# sch2.net
KiCad netlist of a schematic drawn in Altium Designer
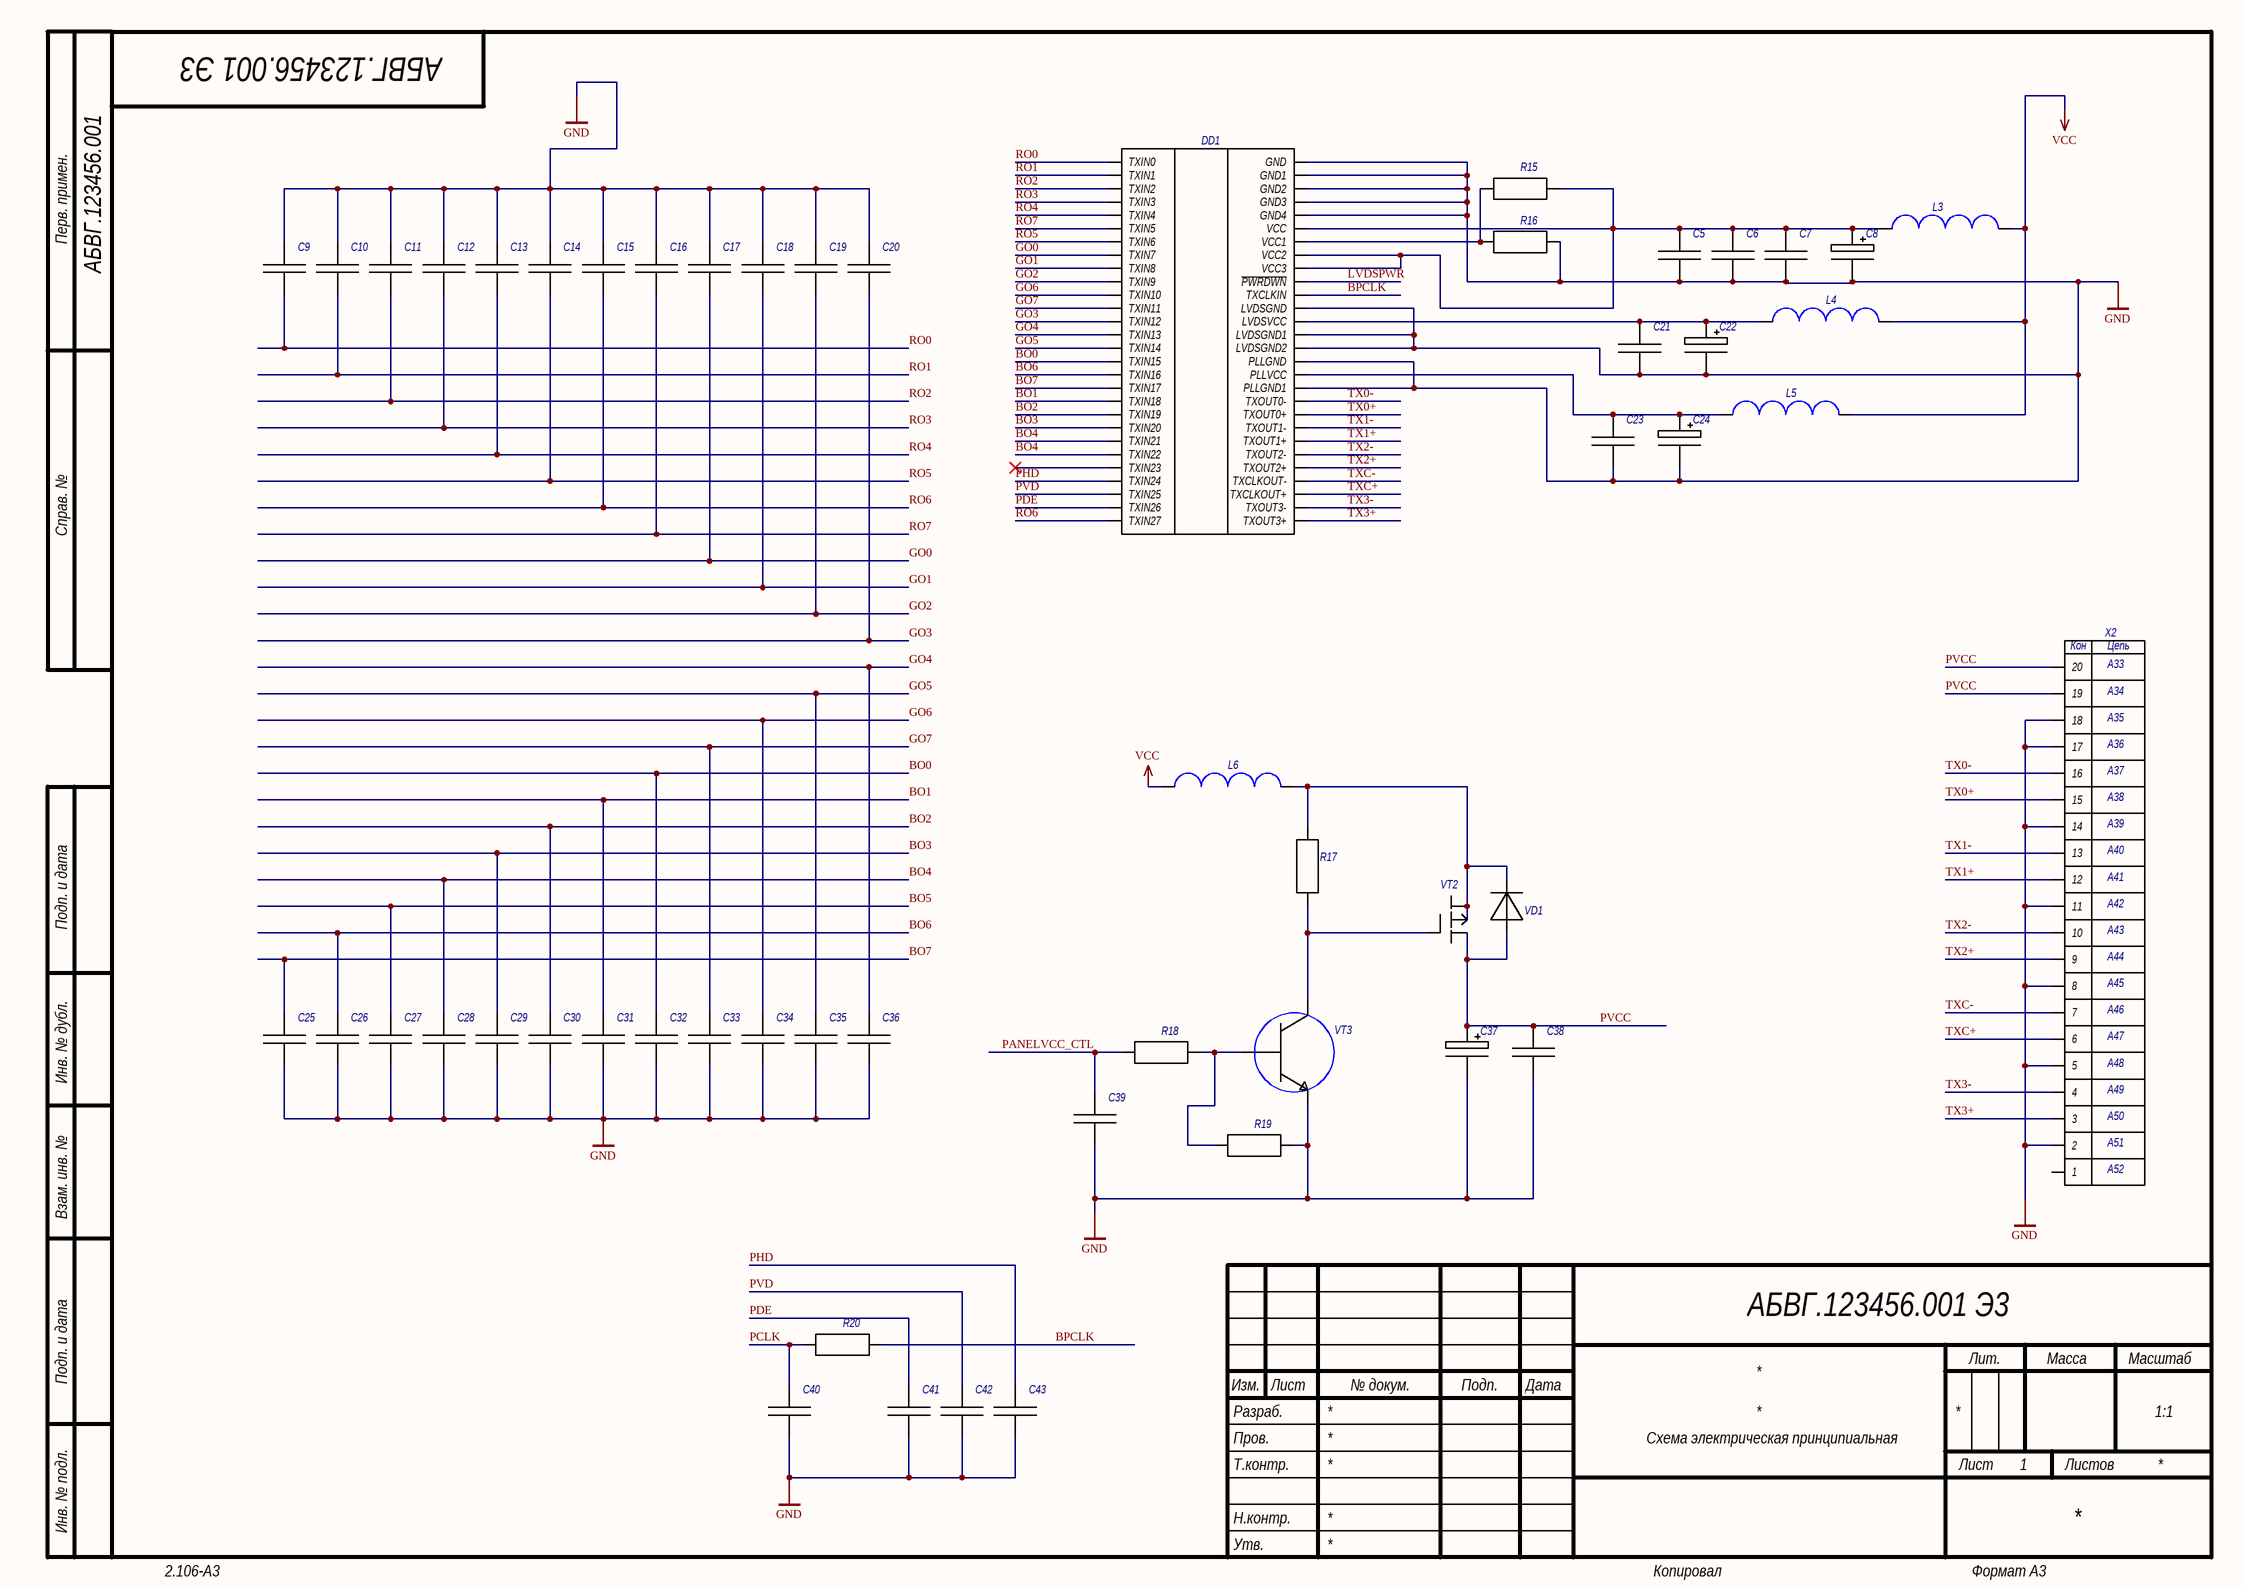
[diagram p0: sch2.SchDoc]

(export (version "E")
  (design (tool "Eeschema 10.0.6"))
  (components
    (comp (ref "C5") (value "*") (footprint "Capacitor 0805") (libsource (lib "k7shared") (part "Capacitor")))
    (comp (ref "C6") (value "*") (footprint "Capacitor 0805") (libsource (lib "k7shared") (part "Capacitor")))
    (comp (ref "C7") (value "*") (footprint "Capacitor 0805") (libsource (lib "k7shared") (part "Capacitor")))
    (comp (ref "C8")
      (value "*")
      (footprint "Capacitor 0805")
      (libsource (lib "k7shared") (part "Capacitor Duga"))
    )
    (comp (ref "C9") (value "*") (footprint "Capacitor 0805") (libsource (lib "k7shared") (part "Capacitor")))
    (comp (ref "C10")
      (value "*")
      (footprint "Capacitor 0805")
      (libsource (lib "k7shared") (part "Capacitor"))
    )
    (comp (ref "C11")
      (value "*")
      (footprint "Capacitor 0805")
      (libsource (lib "k7shared") (part "Capacitor"))
    )
    (comp (ref "C12")
      (value "*")
      (footprint "Capacitor 0805")
      (libsource (lib "k7shared") (part "Capacitor"))
    )
    (comp (ref "C13")
      (value "*")
      (footprint "Capacitor 0805")
      (libsource (lib "k7shared") (part "Capacitor"))
    )
    (comp (ref "C14")
      (value "*")
      (footprint "Capacitor 0805")
      (libsource (lib "k7shared") (part "Capacitor"))
    )
    (comp (ref "C15")
      (value "*")
      (footprint "Capacitor 0805")
      (libsource (lib "k7shared") (part "Capacitor"))
    )
    (comp (ref "C16")
      (value "*")
      (footprint "Capacitor 0805")
      (libsource (lib "k7shared") (part "Capacitor"))
    )
    (comp (ref "C17")
      (value "*")
      (footprint "Capacitor 0805")
      (libsource (lib "k7shared") (part "Capacitor"))
    )
    (comp (ref "C18")
      (value "*")
      (footprint "Capacitor 0805")
      (libsource (lib "k7shared") (part "Capacitor"))
    )
    (comp (ref "C19")
      (value "*")
      (footprint "Capacitor 0805")
      (libsource (lib "k7shared") (part "Capacitor"))
    )
    (comp (ref "C20")
      (value "*")
      (footprint "Capacitor 0805")
      (libsource (lib "k7shared") (part "Capacitor"))
    )
    (comp (ref "C21")
      (value "*")
      (footprint "Capacitor 0805")
      (libsource (lib "k7shared") (part "Capacitor"))
    )
    (comp (ref "C22")
      (value "*")
      (footprint "Capacitor 0805")
      (libsource (lib "k7shared") (part "Capacitor Duga"))
    )
    (comp (ref "C23")
      (value "*")
      (footprint "Capacitor 0805")
      (libsource (lib "k7shared") (part "Capacitor"))
    )
    (comp (ref "C24")
      (value "*")
      (footprint "Capacitor 0805")
      (libsource (lib "k7shared") (part "Capacitor Duga"))
    )
    (comp (ref "C25")
      (value "*")
      (footprint "Capacitor 0805")
      (libsource (lib "k7shared") (part "Capacitor"))
    )
    (comp (ref "C26")
      (value "*")
      (footprint "Capacitor 0805")
      (libsource (lib "k7shared") (part "Capacitor"))
    )
    (comp (ref "C27")
      (value "*")
      (footprint "Capacitor 0805")
      (libsource (lib "k7shared") (part "Capacitor"))
    )
    (comp (ref "C28")
      (value "*")
      (footprint "Capacitor 0805")
      (libsource (lib "k7shared") (part "Capacitor"))
    )
    (comp (ref "C29")
      (value "*")
      (footprint "Capacitor 0805")
      (libsource (lib "k7shared") (part "Capacitor"))
    )
    (comp (ref "C30")
      (value "*")
      (footprint "Capacitor 0805")
      (libsource (lib "k7shared") (part "Capacitor"))
    )
    (comp (ref "C31")
      (value "*")
      (footprint "Capacitor 0805")
      (libsource (lib "k7shared") (part "Capacitor"))
    )
    (comp (ref "C32")
      (value "*")
      (footprint "Capacitor 0805")
      (libsource (lib "k7shared") (part "Capacitor"))
    )
    (comp (ref "C33")
      (value "*")
      (footprint "Capacitor 0805")
      (libsource (lib "k7shared") (part "Capacitor"))
    )
    (comp (ref "C34")
      (value "*")
      (footprint "Capacitor 0805")
      (libsource (lib "k7shared") (part "Capacitor"))
    )
    (comp (ref "C35")
      (value "*")
      (footprint "Capacitor 0805")
      (libsource (lib "k7shared") (part "Capacitor"))
    )
    (comp (ref "C36")
      (value "*")
      (footprint "Capacitor 0805")
      (libsource (lib "k7shared") (part "Capacitor"))
    )
    (comp (ref "C37")
      (value "*")
      (footprint "Capacitor 0805")
      (libsource (lib "k7shared") (part "Capacitor Duga"))
    )
    (comp (ref "C38")
      (value "*")
      (footprint "Capacitor 0805")
      (libsource (lib "k7shared") (part "Capacitor"))
    )
    (comp (ref "C39")
      (value "*")
      (footprint "Capacitor 0805")
      (libsource (lib "k7shared") (part "Capacitor"))
    )
    (comp (ref "C40")
      (value "*")
      (footprint "Capacitor 0805")
      (libsource (lib "k7shared") (part "Capacitor"))
    )
    (comp (ref "C41")
      (value "*")
      (footprint "Capacitor 0805")
      (libsource (lib "k7shared") (part "Capacitor"))
    )
    (comp (ref "C42")
      (value "*")
      (footprint "Capacitor 0805")
      (libsource (lib "k7shared") (part "Capacitor"))
    )
    (comp (ref "C43")
      (value "*")
      (footprint "Capacitor 0805")
      (libsource (lib "k7shared") (part "Capacitor"))
    )
    (comp (ref "DD1") (value "*") (footprint "THC63_1") (libsource (lib "k7sch2") (part "THC63")))
    (comp (ref "L3") (value "*") (footprint "Inductor 2520") (libsource (lib "k7shared") (part "Inductor")))
    (comp (ref "L4") (value "*") (footprint "Inductor 2520") (libsource (lib "k7shared") (part "Inductor")))
    (comp (ref "L5") (value "*") (footprint "Inductor 2520") (libsource (lib "k7shared") (part "Inductor")))
    (comp (ref "L6") (value "*") (footprint "Inductor 2520") (libsource (lib "k7shared") (part "Inductor")))
    (comp (ref "R15") (value "*") (footprint "Resistor 1206") (libsource (lib "k7shared") (part "Resistor")))
    (comp (ref "R16") (value "*") (footprint "Resistor 1206") (libsource (lib "k7shared") (part "Resistor")))
    (comp (ref "R17") (value "*") (footprint "Resistor 1206") (libsource (lib "k7shared") (part "Resistor")))
    (comp (ref "R18") (value "*") (footprint "Resistor 1206") (libsource (lib "k7shared") (part "Resistor")))
    (comp (ref "R19") (value "*") (footprint "Resistor 1206") (libsource (lib "k7shared") (part "Resistor")))
    (comp (ref "R20") (value "*") (footprint "Resistor 1206") (libsource (lib "k7shared") (part "Resistor")))
    (comp (ref "VD1") (value "Diode 1") (footprint "Diode") (libsource (lib "k7shared") (part "Diode 1")))
    (comp (ref "VT2")
      (value "MOP TRANSISTOR")
      (footprint "TR")
      (libsource (lib "k7shared") (part "MOP TRANSISTOR"))
    )
    (comp (ref "VT3")
      (value "*")
      (footprint "Transistor 1")
      (libsource (lib "k7shared") (part "Transistor 1"))
    )
    (comp (ref "X2") (value "*") (footprint "DF14A") (libsource (lib "k7sch2") (part "DF14A")))
  )
  (nets
    (net (code "1") (name "/BO0") (class "Default")
      (node (ref "C32") (pin "2") (pinfunction "2_2") (pintype "passive"))
      (node (ref "DD1") (pin "16") (pinfunction "TXIN15_16") (pintype "passive"))
    )
    (net (code "2") (name "/BO1") (class "Default")
      (node (ref "C31") (pin "2") (pinfunction "2_2") (pintype "passive"))
      (node (ref "DD1") (pin "19") (pinfunction "TXIN18_19") (pintype "passive"))
    )
    (net (code "3") (name "/BO2") (class "Default")
      (node (ref "C30") (pin "2") (pinfunction "2_2") (pintype "passive"))
      (node (ref "DD1") (pin "20") (pinfunction "TXIN19_20") (pintype "passive"))
    )
    (net (code "4") (name "/BO3") (class "Default")
      (node (ref "C29") (pin "2") (pinfunction "2_2") (pintype "passive"))
      (node (ref "DD1") (pin "21") (pinfunction "TXIN20_21") (pintype "passive"))
    )
    (net (code "5") (name "/BO4") (class "Default")
      (node (ref "C28") (pin "2") (pinfunction "2_2") (pintype "passive"))
      (node (ref "DD1") (pin "22") (pinfunction "TXIN21_22") (pintype "passive"))
      (node (ref "DD1") (pin "23") (pinfunction "TXIN22_23") (pintype "passive"))
    )
    (net (code "6") (name "/BO5") (class "Default")
      (node (ref "C27") (pin "2") (pinfunction "2_2") (pintype "passive"))
    )
    (net (code "7") (name "/BO6") (class "Default")
      (node (ref "C26") (pin "2") (pinfunction "2_2") (pintype "passive"))
      (node (ref "DD1") (pin "17") (pinfunction "TXIN16_17") (pintype "passive"))
    )
    (net (code "8") (name "/BO7") (class "Default")
      (node (ref "C25") (pin "2") (pinfunction "2_2") (pintype "passive"))
      (node (ref "DD1") (pin "18") (pinfunction "TXIN17_18") (pintype "passive"))
    )
    (net (code "9") (name "/BPCLK") (class "Default")
      (node (ref "DD1") (pin "46") (pinfunction "TXCLKIN_46") (pintype "passive"))
      (node (ref "R20") (pin "2") (pinfunction "2_2") (pintype "passive"))
    )
    (net (code "10") (name "/GO0") (class "Default")
      (node (ref "C17") (pin "1") (pinfunction "1_1") (pintype "passive"))
      (node (ref "DD1") (pin "8") (pinfunction "TXIN7_8") (pintype "passive"))
    )
    (net (code "11") (name "/GO1") (class "Default")
      (node (ref "C18") (pin "1") (pinfunction "1_1") (pintype "passive"))
      (node (ref "DD1") (pin "9") (pinfunction "TXIN8_9") (pintype "passive"))
    )
    (net (code "12") (name "/GO2") (class "Default")
      (node (ref "C19") (pin "1") (pinfunction "1_1") (pintype "passive"))
      (node (ref "DD1") (pin "10") (pinfunction "TXIN9_10") (pintype "passive"))
    )
    (net (code "13") (name "/GO3") (class "Default")
      (node (ref "C20") (pin "1") (pinfunction "1_1") (pintype "passive"))
      (node (ref "DD1") (pin "13") (pinfunction "TXIN12_13") (pintype "passive"))
    )
    (net (code "14") (name "/GO4") (class "Default")
      (node (ref "C36") (pin "2") (pinfunction "2_2") (pintype "passive"))
      (node (ref "DD1") (pin "14") (pinfunction "TXIN13_14") (pintype "passive"))
    )
    (net (code "15") (name "/GO5") (class "Default")
      (node (ref "C35") (pin "2") (pinfunction "2_2") (pintype "passive"))
      (node (ref "DD1") (pin "15") (pinfunction "TXIN14_15") (pintype "passive"))
    )
    (net (code "16") (name "/GO6") (class "Default")
      (node (ref "C34") (pin "2") (pinfunction "2_2") (pintype "passive"))
      (node (ref "DD1") (pin "11") (pinfunction "TXIN10_11") (pintype "passive"))
    )
    (net (code "17") (name "/GO7") (class "Default")
      (node (ref "C33") (pin "2") (pinfunction "2_2") (pintype "passive"))
      (node (ref "DD1") (pin "12") (pinfunction "TXIN11_12") (pintype "passive"))
    )
    (net (code "18") (name "/LVDSPWR") (class "Default")
      (node (ref "DD1") (pin "47") (pinfunction "~{PWRDWN}_47") (pintype "passive"))
    )
    (net (code "19") (name "/PANELVCC_CTL") (class "Default")
      (node (ref "C39") (pin "2") (pinfunction "2_2") (pintype "passive"))
      (node (ref "R18") (pin "1") (pinfunction "1_1") (pintype "passive"))
    )
    (net (code "20") (name "/PCLK") (class "Default")
      (node (ref "C40") (pin "2") (pinfunction "2_2") (pintype "passive"))
      (node (ref "R20") (pin "1") (pinfunction "1_1") (pintype "passive"))
    )
    (net (code "21") (name "/PDE") (class "Default")
      (node (ref "C41") (pin "2") (pinfunction "2_2") (pintype "passive"))
      (node (ref "DD1") (pin "27") (pinfunction "TXIN26_27") (pintype "passive"))
    )
    (net (code "22") (name "/PHD") (class "Default")
      (node (ref "C43") (pin "2") (pinfunction "2_2") (pintype "passive"))
      (node (ref "DD1") (pin "25") (pinfunction "TXIN24_25") (pintype "passive"))
    )
    (net (code "23") (name "/PVCC") (class "Default")
      (node (ref "C37") (pin "2") (pinfunction "2_2") (pintype "passive"))
      (node (ref "C38") (pin "2") (pinfunction "2_2") (pintype "passive"))
      (node (ref "VD1") (pin "1") (pinfunction "1_1") (pintype "passive"))
      (node (ref "VT2") (pin "2") (pinfunction "2_2") (pintype "passive"))
      (node (ref "X2") (pin "19") (pinfunction "19_19") (pintype "passive"))
      (node (ref "X2") (pin "20") (pinfunction "20_20") (pintype "passive"))
    )
    (net (code "24") (name "/PVD") (class "Default")
      (node (ref "C42") (pin "2") (pinfunction "2_2") (pintype "passive"))
      (node (ref "DD1") (pin "26") (pinfunction "TXIN25_26") (pintype "passive"))
    )
    (net (code "25") (name "/RO0") (class "Default")
      (node (ref "C9") (pin "1") (pinfunction "1_1") (pintype "passive"))
      (node (ref "DD1") (pin "1") (pinfunction "TXIN0_1") (pintype "passive"))
    )
    (net (code "26") (name "/RO1") (class "Default")
      (node (ref "C10") (pin "1") (pinfunction "1_1") (pintype "passive"))
      (node (ref "DD1") (pin "2") (pinfunction "TXIN1_2") (pintype "passive"))
    )
    (net (code "27") (name "/RO2") (class "Default")
      (node (ref "C11") (pin "1") (pinfunction "1_1") (pintype "passive"))
      (node (ref "DD1") (pin "3") (pinfunction "TXIN2_3") (pintype "passive"))
    )
    (net (code "28") (name "/RO3") (class "Default")
      (node (ref "C12") (pin "1") (pinfunction "1_1") (pintype "passive"))
      (node (ref "DD1") (pin "4") (pinfunction "TXIN3_4") (pintype "passive"))
    )
    (net (code "29") (name "/RO4") (class "Default")
      (node (ref "C13") (pin "1") (pinfunction "1_1") (pintype "passive"))
      (node (ref "DD1") (pin "5") (pinfunction "TXIN4_5") (pintype "passive"))
    )
    (net (code "30") (name "/RO5") (class "Default")
      (node (ref "C14") (pin "1") (pinfunction "1_1") (pintype "passive"))
      (node (ref "DD1") (pin "7") (pinfunction "TXIN6_7") (pintype "passive"))
    )
    (net (code "31") (name "/RO6") (class "Default")
      (node (ref "C15") (pin "1") (pinfunction "1_1") (pintype "passive"))
      (node (ref "DD1") (pin "28") (pinfunction "TXIN27_28") (pintype "passive"))
    )
    (net (code "32") (name "/RO7") (class "Default")
      (node (ref "C16") (pin "1") (pinfunction "1_1") (pintype "passive"))
      (node (ref "DD1") (pin "6") (pinfunction "TXIN5_6") (pintype "passive"))
    )
    (net (code "33") (name "/TX0+") (class "Default")
      (node (ref "DD1") (pin "37") (pinfunction "TXOUT0+_37") (pintype "passive"))
      (node (ref "X2") (pin "15") (pinfunction "15_15") (pintype "passive"))
    )
    (net (code "34") (name "/TX0-") (class "Default")
      (node (ref "DD1") (pin "38") (pinfunction "TXOUT0-_38") (pintype "passive"))
      (node (ref "X2") (pin "16") (pinfunction "16_16") (pintype "passive"))
    )
    (net (code "35") (name "/TX1+") (class "Default")
      (node (ref "DD1") (pin "35") (pinfunction "TXOUT1+_35") (pintype "passive"))
      (node (ref "X2") (pin "12") (pinfunction "12_12") (pintype "passive"))
    )
    (net (code "36") (name "/TX1-") (class "Default")
      (node (ref "DD1") (pin "36") (pinfunction "TXOUT1-_36") (pintype "passive"))
      (node (ref "X2") (pin "13") (pinfunction "13_13") (pintype "passive"))
    )
    (net (code "37") (name "/TX2+") (class "Default")
      (node (ref "DD1") (pin "33") (pinfunction "TXOUT2+_33") (pintype "passive"))
      (node (ref "X2") (pin "9") (pinfunction "9_9") (pintype "passive"))
    )
    (net (code "38") (name "/TX2-") (class "Default")
      (node (ref "DD1") (pin "34") (pinfunction "TXOUT2-_34") (pintype "passive"))
      (node (ref "X2") (pin "10") (pinfunction "10_10") (pintype "passive"))
    )
    (net (code "39") (name "/TX3+") (class "Default")
      (node (ref "DD1") (pin "29") (pinfunction "TXOUT3+_29") (pintype "passive"))
      (node (ref "X2") (pin "3") (pinfunction "3_3") (pintype "passive"))
    )
    (net (code "40") (name "/TX3-") (class "Default")
      (node (ref "DD1") (pin "30") (pinfunction "TXOUT3-_30") (pintype "passive"))
      (node (ref "X2") (pin "4") (pinfunction "4_4") (pintype "passive"))
    )
    (net (code "41") (name "/TXC+") (class "Default")
      (node (ref "DD1") (pin "31") (pinfunction "TXCLKOUT+_31") (pintype "passive"))
      (node (ref "X2") (pin "6") (pinfunction "6_6") (pintype "passive"))
    )
    (net (code "42") (name "/TXC-") (class "Default")
      (node (ref "DD1") (pin "32") (pinfunction "TXCLKOUT-_32") (pintype "passive"))
      (node (ref "X2") (pin "7") (pinfunction "7_7") (pintype "passive"))
    )
    (net (code "43") (name "GND") (class "Default")
      (node (ref "C10") (pin "2") (pinfunction "2_2") (pintype "passive"))
      (node (ref "C11") (pin "2") (pinfunction "2_2") (pintype "passive"))
      (node (ref "C12") (pin "2") (pinfunction "2_2") (pintype "passive"))
      (node (ref "C13") (pin "2") (pinfunction "2_2") (pintype "passive"))
      (node (ref "C14") (pin "2") (pinfunction "2_2") (pintype "passive"))
      (node (ref "C15") (pin "2") (pinfunction "2_2") (pintype "passive"))
      (node (ref "C16") (pin "2") (pinfunction "2_2") (pintype "passive"))
      (node (ref "C17") (pin "2") (pinfunction "2_2") (pintype "passive"))
      (node (ref "C18") (pin "2") (pinfunction "2_2") (pintype "passive"))
      (node (ref "C19") (pin "2") (pinfunction "2_2") (pintype "passive"))
      (node (ref "C20") (pin "2") (pinfunction "2_2") (pintype "passive"))
      (node (ref "C21") (pin "1") (pinfunction "1_1") (pintype "passive"))
      (node (ref "C22") (pin "1") (pinfunction "1_1") (pintype "passive"))
      (node (ref "C23") (pin "1") (pinfunction "1_1") (pintype "passive"))
      (node (ref "C24") (pin "1") (pinfunction "1_1") (pintype "passive"))
      (node (ref "C25") (pin "1") (pinfunction "1_1") (pintype "passive"))
      (node (ref "C26") (pin "1") (pinfunction "1_1") (pintype "passive"))
      (node (ref "C27") (pin "1") (pinfunction "1_1") (pintype "passive"))
      (node (ref "C28") (pin "1") (pinfunction "1_1") (pintype "passive"))
      (node (ref "C29") (pin "1") (pinfunction "1_1") (pintype "passive"))
      (node (ref "C30") (pin "1") (pinfunction "1_1") (pintype "passive"))
      (node (ref "C31") (pin "1") (pinfunction "1_1") (pintype "passive"))
      (node (ref "C32") (pin "1") (pinfunction "1_1") (pintype "passive"))
      (node (ref "C33") (pin "1") (pinfunction "1_1") (pintype "passive"))
      (node (ref "C34") (pin "1") (pinfunction "1_1") (pintype "passive"))
      (node (ref "C35") (pin "1") (pinfunction "1_1") (pintype "passive"))
      (node (ref "C36") (pin "1") (pinfunction "1_1") (pintype "passive"))
      (node (ref "C37") (pin "1") (pinfunction "1_1") (pintype "passive"))
      (node (ref "C38") (pin "1") (pinfunction "1_1") (pintype "passive"))
      (node (ref "C39") (pin "1") (pinfunction "1_1") (pintype "passive"))
      (node (ref "C40") (pin "1") (pinfunction "1_1") (pintype "passive"))
      (node (ref "C41") (pin "1") (pinfunction "1_1") (pintype "passive"))
      (node (ref "C42") (pin "1") (pinfunction "1_1") (pintype "passive"))
      (node (ref "C43") (pin "1") (pinfunction "1_1") (pintype "passive"))
      (node (ref "C5") (pin "1") (pinfunction "1_1") (pintype "passive"))
      (node (ref "C6") (pin "1") (pinfunction "1_1") (pintype "passive"))
      (node (ref "C7") (pin "1") (pinfunction "1_1") (pintype "passive"))
      (node (ref "C8") (pin "1") (pinfunction "1_1") (pintype "passive"))
      (node (ref "C9") (pin "2") (pinfunction "2_2") (pintype "passive"))
      (node (ref "DD1") (pin "39") (pinfunction "PLLGND1_39") (pintype "passive"))
      (node (ref "DD1") (pin "41") (pinfunction "PLLGND_41") (pintype "passive"))
      (node (ref "DD1") (pin "42") (pinfunction "LVDSGND2_42") (pintype "passive"))
      (node (ref "DD1") (pin "43") (pinfunction "LVDSGND1_43") (pintype "passive"))
      (node (ref "DD1") (pin "45") (pinfunction "LVDSGND_45") (pintype "passive"))
      (node (ref "DD1") (pin "52") (pinfunction "GND4_52") (pintype "passive"))
      (node (ref "DD1") (pin "53") (pinfunction "GND3_53") (pintype "passive"))
      (node (ref "DD1") (pin "54") (pinfunction "GND2_54") (pintype "passive"))
      (node (ref "DD1") (pin "55") (pinfunction "GND1_55") (pintype "passive"))
      (node (ref "DD1") (pin "56") (pinfunction "GND_56") (pintype "passive"))
      (node (ref "R16") (pin "2") (pinfunction "2_2") (pintype "passive"))
      (node (ref "R19") (pin "2") (pinfunction "2_2") (pintype "passive"))
      (node (ref "VT3") (pin "1") (pinfunction "KOLLECTOR_1") (pintype "passive"))
      (node (ref "X2") (pin "11") (pinfunction "11_11") (pintype "passive"))
      (node (ref "X2") (pin "14") (pinfunction "14_14") (pintype "passive"))
      (node (ref "X2") (pin "17") (pinfunction "17_17") (pintype "passive"))
      (node (ref "X2") (pin "18") (pinfunction "18_18") (pintype "passive"))
      (node (ref "X2") (pin "2") (pinfunction "2_2") (pintype "passive"))
      (node (ref "X2") (pin "5") (pinfunction "5_5") (pintype "passive"))
      (node (ref "X2") (pin "8") (pinfunction "8_8") (pintype "passive"))
    )
    (net (code "44") (name "Net-(DD1-LVDSVCC)") (class "Default")
      (node (ref "C21") (pin "2") (pinfunction "2_2") (pintype "passive"))
      (node (ref "C22") (pin "2") (pinfunction "2_2") (pintype "passive"))
      (node (ref "DD1") (pin "44") (pinfunction "LVDSVCC_44") (pintype "passive"))
      (node (ref "L4") (pin "1") (pinfunction "1_1") (pintype "passive"))
    )
    (net (code "45") (name "Net-(DD1-PLLVCC)") (class "Default")
      (node (ref "C23") (pin "2") (pinfunction "2_2") (pintype "passive"))
      (node (ref "C24") (pin "2") (pinfunction "2_2") (pintype "passive"))
      (node (ref "DD1") (pin "40") (pinfunction "PLLVCC_40") (pintype "passive"))
      (node (ref "L5") (pin "1") (pinfunction "1_1") (pintype "passive"))
    )
    (net (code "46") (name "Net-(DD1-VCC)") (class "Default")
      (node (ref "C5") (pin "2") (pinfunction "2_2") (pintype "passive"))
      (node (ref "C6") (pin "2") (pinfunction "2_2") (pintype "passive"))
      (node (ref "C7") (pin "2") (pinfunction "2_2") (pintype "passive"))
      (node (ref "C8") (pin "2") (pinfunction "2_2") (pintype "passive"))
      (node (ref "DD1") (pin "48") (pinfunction "VCC3_48") (pintype "passive"))
      (node (ref "DD1") (pin "49") (pinfunction "VCC2_49") (pintype "passive"))
      (node (ref "DD1") (pin "51") (pinfunction "VCC_51") (pintype "passive"))
      (node (ref "L3") (pin "1") (pinfunction "1_1") (pintype "passive"))
      (node (ref "R15") (pin "2") (pinfunction "2_2") (pintype "passive"))
    )
    (net (code "47") (name "Net-(DD1-VCC1)") (class "Default")
      (node (ref "DD1") (pin "50") (pinfunction "VCC1_50") (pintype "passive"))
      (node (ref "R15") (pin "1") (pinfunction "1_1") (pintype "passive"))
      (node (ref "R16") (pin "1") (pinfunction "1_1") (pintype "passive"))
    )
    (net (code "48") (name "Net-(L6-Pad2)") (class "Default")
      (node (ref "L6") (pin "2") (pinfunction "2_2") (pintype "passive"))
      (node (ref "R17") (pin "2") (pinfunction "2_2") (pintype "passive"))
      (node (ref "VD1") (pin "2") (pinfunction "2_2") (pintype "passive"))
      (node (ref "VT2") (pin "3") (pinfunction "3_3") (pintype "passive"))
      (node (ref "VT2") (pin "4") (pinfunction "4_4") (pintype "passive"))
    )
    (net (code "49") (name "Net-(VT3-BAZA)") (class "Default")
      (node (ref "R18") (pin "2") (pinfunction "2_2") (pintype "passive"))
      (node (ref "R19") (pin "1") (pinfunction "1_1") (pintype "passive"))
      (node (ref "VT3") (pin "3") (pinfunction "BAZA_3") (pintype "passive"))
    )
    (net (code "50") (name "Net-(VT3-EMITTER)") (class "Default")
      (node (ref "R17") (pin "1") (pinfunction "1_1") (pintype "passive"))
      (node (ref "VT2") (pin "1") (pinfunction "1_1") (pintype "passive"))
      (node (ref "VT3") (pin "2") (pinfunction "EMITTER_2") (pintype "passive"))
    )
    (net (code "51") (name "VCC") (class "Default")
      (node (ref "L3") (pin "2") (pinfunction "2_2") (pintype "passive"))
      (node (ref "L4") (pin "2") (pinfunction "2_2") (pintype "passive"))
      (node (ref "L5") (pin "2") (pinfunction "2_2") (pintype "passive"))
      (node (ref "L6") (pin "1") (pinfunction "1_1") (pintype "passive"))
    )
    (net (code "52") (name "unconnected-(DD1-TXIN23-Pad24)") (class "Default")
      (node (ref "DD1") (pin "24") (pinfunction "TXIN23_24") (pintype "passive+no_connect"))
    )
    (net (code "53") (name "unconnected-(X2-Pad1)") (class "Default")
      (node (ref "X2") (pin "1") (pinfunction "1_1") (pintype "passive"))
    )
  )
)
